# Gate_Drive.net
KiCad netlist of a schematic drawn in Altium Designer
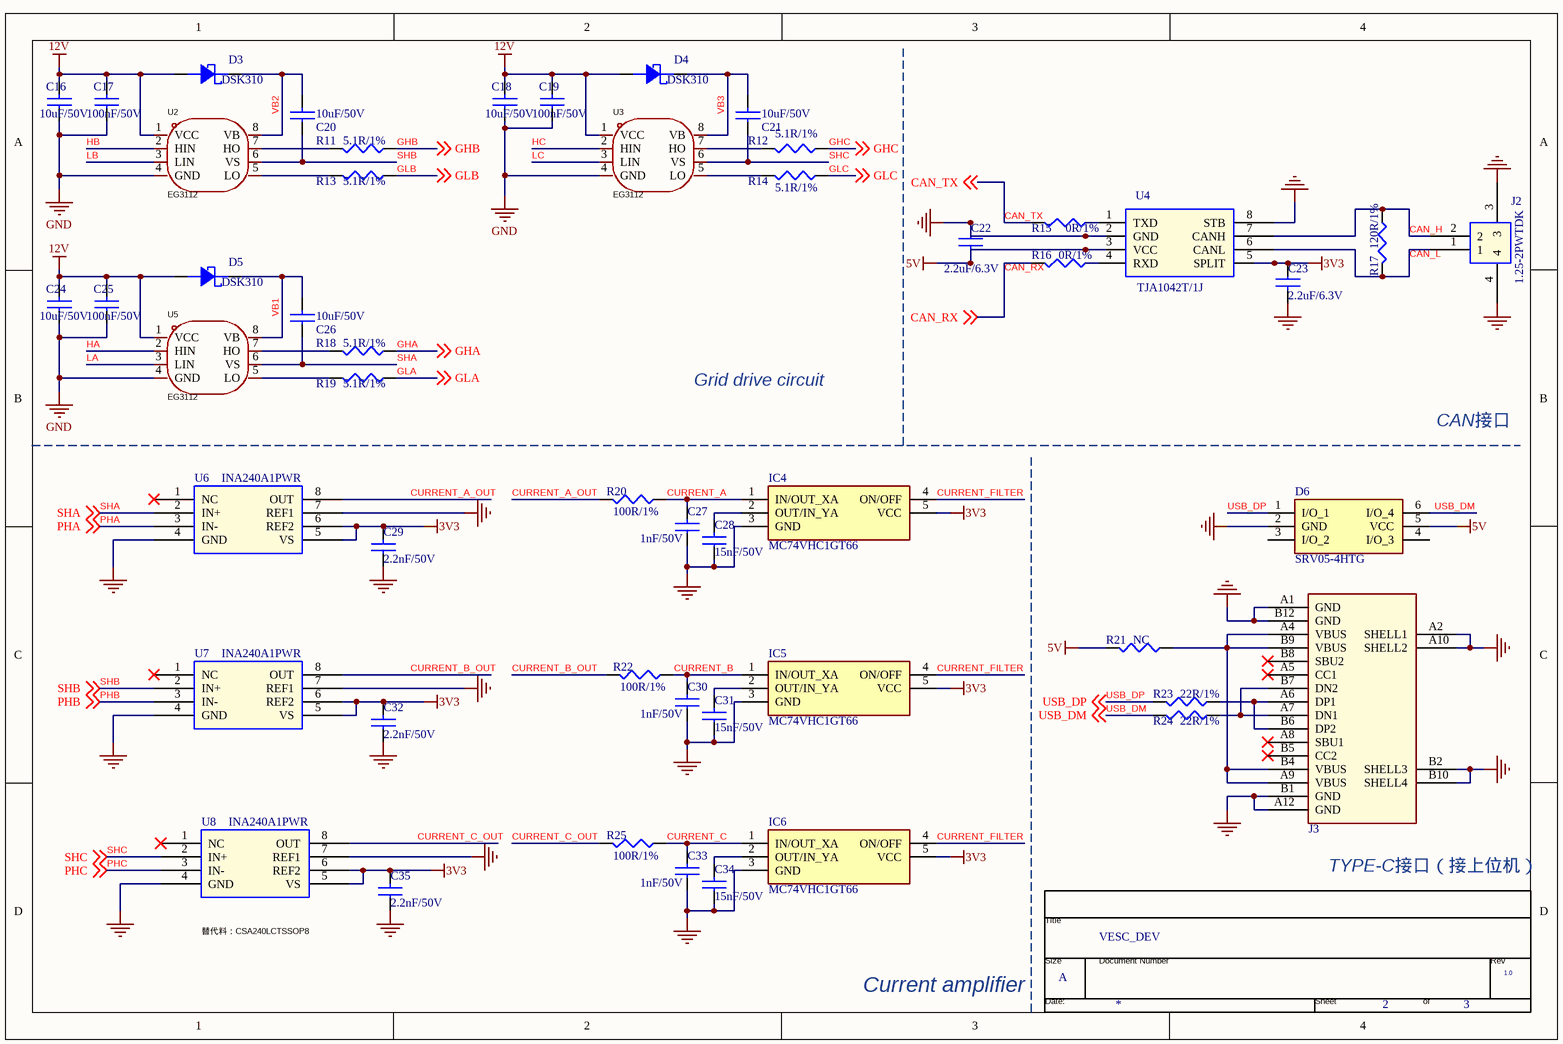
[diagram p0: Gate_Drive.SchDoc]

(export (version "E")
  (design (tool "Eeschema 10.0.6"))
  (components
    (comp (ref "C16") (value "10uF/50V") (footprint "C0603") (libsource (lib "*") (part "CAP NP")))
    (comp (ref "C17") (value "100nF/50V") (footprint "C0603") (libsource (lib "*") (part "CAP NP")))
    (comp (ref "C18") (value "10uF/50V") (footprint "C0603") (libsource (lib "*") (part "CAP NP")))
    (comp (ref "C19") (value "100nF/50V") (footprint "C0603") (libsource (lib "*") (part "CAP NP")))
    (comp (ref "C20") (value "10uF/50V") (footprint "C0603") (libsource (lib "*") (part "CAP NP")))
    (comp (ref "C21") (value "10uF/50V") (footprint "C0603") (libsource (lib "*") (part "CAP NP")))
    (comp (ref "C22") (value "2.2uF/6.3V") (footprint "C0402") (libsource (lib "*") (part "CAP NP")))
    (comp (ref "C23") (value "2.2uF/6.3V") (footprint "C0402") (libsource (lib "*") (part "CAP NP")))
    (comp (ref "C24") (value "10uF/50V") (footprint "C0603") (libsource (lib "*") (part "CAP NP")))
    (comp (ref "C25") (value "100nF/50V") (footprint "C0603") (libsource (lib "*") (part "CAP NP")))
    (comp (ref "C26") (value "10uF/50V") (footprint "C0603") (libsource (lib "*") (part "CAP NP")))
    (comp (ref "C27") (value "1nF/50V") (footprint "C0402") (libsource (lib "*") (part "CAP NP")))
    (comp (ref "C28") (value "15nF/50V") (footprint "C0402") (libsource (lib "*") (part "CAP NP")))
    (comp (ref "C29") (value "2.2nF/50V") (footprint "C0402") (libsource (lib "*") (part "CAP NP")))
    (comp (ref "C30") (value "1nF/50V") (footprint "C0402") (libsource (lib "*") (part "CAP NP")))
    (comp (ref "C31") (value "15nF/50V") (footprint "C0402") (libsource (lib "*") (part "CAP NP")))
    (comp (ref "C32") (value "2.2nF/50V") (footprint "C0402") (libsource (lib "*") (part "CAP NP")))
    (comp (ref "C33") (value "1nF/50V") (footprint "C0402") (libsource (lib "*") (part "CAP NP")))
    (comp (ref "C34") (value "15nF/50V") (footprint "C0402") (libsource (lib "*") (part "CAP NP")))
    (comp (ref "C35") (value "2.2nF/50V") (footprint "C0402") (libsource (lib "*") (part "CAP NP")))
    (comp (ref "D3") (value "DSK310") (footprint "SOD-123F") (libsource (lib "*") (part "DIODE SCHOTTKY21")))
    (comp (ref "D4") (value "DSK310") (footprint "SOD-123F") (libsource (lib "*") (part "DIODE SCHOTTKY21")))
    (comp (ref "D5") (value "DSK310") (footprint "SOD-123F") (libsource (lib "*") (part "DIODE SCHOTTKY21")))
    (comp (ref "D6")
      (value "SRV05-4HTG")
      (footprint "SamacSys:SOT95P280X145-6N")
      (description "TVS Diode (Uni-directional)")
      (fields (field (name "MOUSER PART NUMBER") "576-SRV05-4HTG"))
      (libsource (lib "VESC_DEVICE_Library") (part "SRV05-4HTG"))
    )
    (comp (ref "IC4")
      (value "MC74VHC1GT66")
      (footprint "SamacSys:SOT95P275X110-5N")
      (description "Integrated Circuit")
      (libsource (lib "VESC_DEVICE_Library") (part "MC74VHC1GT66"))
    )
    (comp (ref "IC5")
      (value "MC74VHC1GT66")
      (footprint "SamacSys:SOT95P275X110-5N")
      (description "Integrated Circuit")
      (libsource (lib "VESC_DEVICE_Library") (part "MC74VHC1GT66"))
    )
    (comp (ref "IC6")
      (value "MC74VHC1GT66")
      (footprint "SamacSys:SOT95P275X110-5N")
      (description "Integrated Circuit")
      (libsource (lib "VESC_DEVICE_Library") (part "MC74VHC1GT66"))
    )
    (comp (ref "J2")
      (value "1.25-2PWTDK")
      (footprint "SMD-2P-1_25")
      (libsource (lib "*") (part "1.25-2PWTDK"))
    )
    (comp (ref "J3")
      (value "TYPE-C 16PLC-H10.0")
      (footprint "TYPE-C-TH_16PLC-H10.0")
      (description "连接器类型:Type-C;标准:USB 3.1;公母:母;安装方式:直插;触点数量:16P;端口数量:1;额定电流 - 电源:5A;触头材质:-;触头镀层:-;工作温度范围:-40℃~+85℃;")
      (fields (field (name "MANUFACTURER") "SHOU HAN(首韩)"))
      (libsource (lib "VESC_DEVICE_Library") (part "TYPE-C 16PLC-H10.0"))
    )
    (comp (ref "R11") (value "5.1R/1%") (footprint "R0603") (libsource (lib "*") (part "RESISTOR")))
    (comp (ref "R12") (value "5.1R/1%") (footprint "R0603") (libsource (lib "*") (part "RESISTOR")))
    (comp (ref "R13") (value "5.1R/1%") (footprint "R0603") (libsource (lib "*") (part "RESISTOR")))
    (comp (ref "R14") (value "5.1R/1%") (footprint "R0603") (libsource (lib "*") (part "RESISTOR")))
    (comp (ref "R15") (value "0R/1%") (footprint "R0402") (libsource (lib "*") (part "RESISTOR")))
    (comp (ref "R16") (value "0R/1%") (footprint "R0402") (libsource (lib "*") (part "RESISTOR")))
    (comp (ref "R17") (value "120R/1%") (footprint "R0402") (libsource (lib "*") (part "RESISTOR")))
    (comp (ref "R18") (value "5.1R/1%") (footprint "R0603") (libsource (lib "*") (part "RESISTOR")))
    (comp (ref "R19") (value "5.1R/1%") (footprint "R0603") (libsource (lib "*") (part "RESISTOR")))
    (comp (ref "R20") (value "100R/1%") (footprint "R0402") (libsource (lib "*") (part "RESISTOR")))
    (comp (ref "R21") (value "NC") (footprint "R0603") (libsource (lib "*") (part "RESISTOR")))
    (comp (ref "R22") (value "100R/1%") (footprint "R0402") (libsource (lib "*") (part "RESISTOR")))
    (comp (ref "R23") (value "22R/1%") (footprint "R0402") (libsource (lib "*") (part "RESISTOR")))
    (comp (ref "R24") (value "22R/1%") (footprint "R0402") (libsource (lib "*") (part "RESISTOR")))
    (comp (ref "R25") (value "100R/1%") (footprint "R0402") (libsource (lib "*") (part "RESISTOR")))
    (comp (ref "U2")
      (value "EG3112")
      (footprint "SOIC-8_L4.9-W3.9-P1.27-LS6.0-BL")
      (fields (field (name "MANUFACTURER") "EG(屹晶微)"))
      (libsource (lib "VESC_DEVICE_Library") (part "EG3112"))
    )
    (comp (ref "U3")
      (value "EG3112")
      (footprint "SOIC-8_L4.9-W3.9-P1.27-LS6.0-BL")
      (fields (field (name "MANUFACTURER") "EG(屹晶微)"))
      (libsource (lib "VESC_DEVICE_Library") (part "EG3112"))
    )
    (comp (ref "U4") (value "TJA1042T/1J") (footprint "SOP-8") (libsource (lib "*") (part "TJA1042T/1J")))
    (comp (ref "U5")
      (value "EG3112")
      (footprint "SOIC-8_L4.9-W3.9-P1.27-LS6.0-BL")
      (fields (field (name "MANUFACTURER") "EG(屹晶微)"))
      (libsource (lib "VESC_DEVICE_Library") (part "EG3112"))
    )
    (comp (ref "U6") (value "INA240A1PWR") (footprint "TSSOP-8") (libsource (lib "*") (part "INA240A1PWR")))
    (comp (ref "U7") (value "INA240A1PWR") (footprint "TSSOP-8") (libsource (lib "*") (part "INA240A1PWR")))
    (comp (ref "U8") (value "INA240A1PWR") (footprint "TSSOP-8") (libsource (lib "*") (part "INA240A1PWR")))
  )
  (nets
    (net (code "1") (name "/CAN_H") (class "Default")
      (node (ref "J2") (pin "2") (pinfunction "2_2") (pintype "passive"))
      (node (ref "R17") (pin "1") (pinfunction "1_1") (pintype "passive"))
      (node (ref "U4") (pin "7") (pinfunction "CANH_7") (pintype "passive"))
    )
    (net (code "2") (name "/CAN_L") (class "Default")
      (node (ref "J2") (pin "1") (pinfunction "1_1") (pintype "passive"))
      (node (ref "R17") (pin "2") (pinfunction "2_2") (pintype "passive"))
      (node (ref "U4") (pin "6") (pinfunction "CANL_6") (pintype "passive"))
    )
    (net (code "3") (name "/CURRENT_A") (class "Default")
      (node (ref "C27") (pin "2") (pinfunction "2_2") (pintype "passive"))
      (node (ref "IC4") (pin "1") (pinfunction "IN/OUT_XA_1") (pintype "passive"))
      (node (ref "R20") (pin "1") (pinfunction "1_1") (pintype "passive"))
    )
    (net (code "4") (name "/CURRENT_A_OUT") (class "Default")
      (node (ref "R20") (pin "2") (pinfunction "2_2") (pintype "passive"))
      (node (ref "U6") (pin "8") (pinfunction "OUT_8") (pintype "passive"))
    )
    (net (code "5") (name "/CURRENT_B") (class "Default")
      (node (ref "C30") (pin "2") (pinfunction "2_2") (pintype "passive"))
      (node (ref "IC5") (pin "1") (pinfunction "IN/OUT_XA_1") (pintype "passive"))
      (node (ref "R22") (pin "1") (pinfunction "1_1") (pintype "passive"))
    )
    (net (code "6") (name "/CURRENT_B_OUT") (class "Default")
      (node (ref "R22") (pin "2") (pinfunction "2_2") (pintype "passive"))
      (node (ref "U7") (pin "8") (pinfunction "OUT_8") (pintype "passive"))
    )
    (net (code "7") (name "/CURRENT_C") (class "Default")
      (node (ref "C33") (pin "2") (pinfunction "2_2") (pintype "passive"))
      (node (ref "IC6") (pin "1") (pinfunction "IN/OUT_XA_1") (pintype "passive"))
      (node (ref "R25") (pin "1") (pinfunction "1_1") (pintype "passive"))
    )
    (net (code "8") (name "/CURRENT_C_OUT") (class "Default")
      (node (ref "R25") (pin "2") (pinfunction "2_2") (pintype "passive"))
      (node (ref "U8") (pin "8") (pinfunction "OUT_8") (pintype "passive"))
    )
    (net (code "9") (name "/CURRENT_FILTER") (class "Default")
      (node (ref "IC4") (pin "4") (pinfunction "ON/OFF_4") (pintype "passive"))
      (node (ref "IC5") (pin "4") (pinfunction "ON/OFF_4") (pintype "passive"))
      (node (ref "IC6") (pin "4") (pinfunction "ON/OFF_4") (pintype "passive"))
    )
    (net (code "10") (name "/HA") (class "Default")
      (node (ref "U5") (pin "2") (pinfunction "HIN_2") (pintype "passive"))
    )
    (net (code "11") (name "/HB") (class "Default")
      (node (ref "U2") (pin "2") (pinfunction "HIN_2") (pintype "passive"))
    )
    (net (code "12") (name "/HC") (class "Default")
      (node (ref "U3") (pin "2") (pinfunction "HIN_2") (pintype "passive"))
    )
    (net (code "13") (name "/LA") (class "Default")
      (node (ref "U5") (pin "3") (pinfunction "LIN_3") (pintype "passive"))
    )
    (net (code "14") (name "/LB") (class "Default")
      (node (ref "U2") (pin "3") (pinfunction "LIN_3") (pintype "passive"))
    )
    (net (code "15") (name "/LC") (class "Default")
      (node (ref "U3") (pin "3") (pinfunction "LIN_3") (pintype "passive"))
    )
    (net (code "16") (name "/VB1") (class "Default")
      (node (ref "C26") (pin "2") (pinfunction "2_2") (pintype "passive"))
      (node (ref "D5") (pin "1") (pinfunction "K_1") (pintype "passive"))
      (node (ref "U5") (pin "8") (pinfunction "VB_8") (pintype "passive"))
    )
    (net (code "17") (name "/VB2") (class "Default")
      (node (ref "C20") (pin "2") (pinfunction "2_2") (pintype "passive"))
      (node (ref "D3") (pin "1") (pinfunction "K_1") (pintype "passive"))
      (node (ref "U2") (pin "8") (pinfunction "VB_8") (pintype "passive"))
    )
    (net (code "18") (name "/VB3") (class "Default")
      (node (ref "C21") (pin "2") (pinfunction "2_2") (pintype "passive"))
      (node (ref "D4") (pin "1") (pinfunction "K_1") (pintype "passive"))
      (node (ref "U3") (pin "8") (pinfunction "VB_8") (pintype "passive"))
    )
    (net (code "19") (name "3V3") (class "Default")
      (node (ref "C23") (pin "1") (pinfunction "1_1") (pintype "passive"))
      (node (ref "C29") (pin "2") (pinfunction "2_2") (pintype "passive"))
      (node (ref "C32") (pin "2") (pinfunction "2_2") (pintype "passive"))
      (node (ref "C35") (pin "2") (pinfunction "2_2") (pintype "passive"))
      (node (ref "IC4") (pin "5") (pinfunction "VCC_5") (pintype "passive"))
      (node (ref "IC5") (pin "5") (pinfunction "VCC_5") (pintype "passive"))
      (node (ref "IC6") (pin "5") (pinfunction "VCC_5") (pintype "passive"))
      (node (ref "U4") (pin "5") (pinfunction "SPLIT_5") (pintype "passive"))
      (node (ref "U6") (pin "5") (pinfunction "VS_5") (pintype "passive"))
      (node (ref "U6") (pin "6") (pinfunction "REF2_6") (pintype "passive"))
      (node (ref "U7") (pin "5") (pinfunction "VS_5") (pintype "passive"))
      (node (ref "U7") (pin "6") (pinfunction "REF2_6") (pintype "passive"))
      (node (ref "U8") (pin "5") (pinfunction "VS_5") (pintype "passive"))
      (node (ref "U8") (pin "6") (pinfunction "REF2_6") (pintype "passive"))
    )
    (net (code "20") (name "5V") (class "Default")
      (node (ref "C22") (pin "2") (pinfunction "2_2") (pintype "passive"))
      (node (ref "D6") (pin "5") (pinfunction "VCC_5") (pintype "passive"))
      (node (ref "R21") (pin "2") (pinfunction "2_2") (pintype "passive"))
      (node (ref "U4") (pin "3") (pinfunction "VCC_3") (pintype "passive"))
    )
    (net (code "21") (name "12V") (class "Default")
      (node (ref "C16") (pin "2") (pinfunction "2_2") (pintype "passive"))
      (node (ref "C17") (pin "2") (pinfunction "2_2") (pintype "passive"))
      (node (ref "C18") (pin "2") (pinfunction "2_2") (pintype "passive"))
      (node (ref "C19") (pin "2") (pinfunction "2_2") (pintype "passive"))
      (node (ref "C24") (pin "2") (pinfunction "2_2") (pintype "passive"))
      (node (ref "C25") (pin "2") (pinfunction "2_2") (pintype "passive"))
      (node (ref "D3") (pin "2") (pinfunction "A_2") (pintype "passive"))
      (node (ref "D4") (pin "2") (pinfunction "A_2") (pintype "passive"))
      (node (ref "D5") (pin "2") (pinfunction "A_2") (pintype "passive"))
      (node (ref "U2") (pin "1") (pinfunction "VCC_1") (pintype "passive"))
      (node (ref "U3") (pin "1") (pinfunction "VCC_1") (pintype "passive"))
      (node (ref "U5") (pin "1") (pinfunction "VCC_1") (pintype "passive"))
    )
    (net (code "22") (name "CAN_RX") (class "Default")
      (node (ref "R16") (pin "2") (pinfunction "2_2") (pintype "passive"))
    )
    (net (code "23") (name "CAN_TX") (class "Default")
      (node (ref "R15") (pin "2") (pinfunction "2_2") (pintype "passive"))
    )
    (net (code "24") (name "GHA") (class "Default")
      (node (ref "R18") (pin "1") (pinfunction "1_1") (pintype "passive"))
    )
    (net (code "25") (name "GHB") (class "Default")
      (node (ref "R11") (pin "1") (pinfunction "1_1") (pintype "passive"))
    )
    (net (code "26") (name "GHC") (class "Default")
      (node (ref "R12") (pin "1") (pinfunction "1_1") (pintype "passive"))
    )
    (net (code "27") (name "GLA") (class "Default")
      (node (ref "R19") (pin "1") (pinfunction "1_1") (pintype "passive"))
    )
    (net (code "28") (name "GLB") (class "Default")
      (node (ref "R13") (pin "1") (pinfunction "1_1") (pintype "passive"))
    )
    (net (code "29") (name "GLC") (class "Default")
      (node (ref "R14") (pin "1") (pinfunction "1_1") (pintype "passive"))
    )
    (net (code "30") (name "GND") (class "Default")
      (node (ref "C16") (pin "1") (pinfunction "1_1") (pintype "passive"))
      (node (ref "C17") (pin "1") (pinfunction "1_1") (pintype "passive"))
      (node (ref "C18") (pin "1") (pinfunction "1_1") (pintype "passive"))
      (node (ref "C19") (pin "1") (pinfunction "1_1") (pintype "passive"))
      (node (ref "C22") (pin "1") (pinfunction "1_1") (pintype "passive"))
      (node (ref "C23") (pin "2") (pinfunction "2_2") (pintype "passive"))
      (node (ref "C24") (pin "1") (pinfunction "1_1") (pintype "passive"))
      (node (ref "C25") (pin "1") (pinfunction "1_1") (pintype "passive"))
      (node (ref "C27") (pin "1") (pinfunction "1_1") (pintype "passive"))
      (node (ref "C28") (pin "1") (pinfunction "1_1") (pintype "passive"))
      (node (ref "C29") (pin "1") (pinfunction "1_1") (pintype "passive"))
      (node (ref "C30") (pin "1") (pinfunction "1_1") (pintype "passive"))
      (node (ref "C31") (pin "1") (pinfunction "1_1") (pintype "passive"))
      (node (ref "C32") (pin "1") (pinfunction "1_1") (pintype "passive"))
      (node (ref "C33") (pin "1") (pinfunction "1_1") (pintype "passive"))
      (node (ref "C34") (pin "1") (pinfunction "1_1") (pintype "passive"))
      (node (ref "C35") (pin "1") (pinfunction "1_1") (pintype "passive"))
      (node (ref "D6") (pin "2") (pinfunction "GND_2") (pintype "passive"))
      (node (ref "IC4") (pin "3") (pinfunction "GND_3") (pintype "passive"))
      (node (ref "IC5") (pin "3") (pinfunction "GND_3") (pintype "passive"))
      (node (ref "IC6") (pin "3") (pinfunction "GND_3") (pintype "passive"))
      (node (ref "J2") (pin "3") (pinfunction "3_3") (pintype "passive"))
      (node (ref "J2") (pin "4") (pinfunction "4_4") (pintype "passive"))
      (node (ref "J3") (pin "A1") (pinfunction "GND_A1") (pintype "power_in"))
      (node (ref "J3") (pin "A10") (pinfunction "SHELL2_A10") (pintype "power_in"))
      (node (ref "J3") (pin "A12") (pinfunction "GND_A12") (pintype "power_in"))
      (node (ref "J3") (pin "A2") (pinfunction "SHELL1_A2") (pintype "power_in"))
      (node (ref "J3") (pin "B1") (pinfunction "GND_B1") (pintype "power_in"))
      (node (ref "J3") (pin "B10") (pinfunction "SHELL4_B10") (pintype "power_in"))
      (node (ref "J3") (pin "B12") (pinfunction "GND_B12") (pintype "power_in"))
      (node (ref "J3") (pin "B2") (pinfunction "SHELL3_B2") (pintype "power_in"))
      (node (ref "U2") (pin "4") (pinfunction "GND_4") (pintype "passive"))
      (node (ref "U3") (pin "4") (pinfunction "GND_4") (pintype "passive"))
      (node (ref "U4") (pin "2") (pinfunction "GND_2") (pintype "passive"))
      (node (ref "U4") (pin "8") (pinfunction "STB_8") (pintype "passive"))
      (node (ref "U5") (pin "4") (pinfunction "GND_4") (pintype "passive"))
      (node (ref "U6") (pin "4") (pinfunction "GND_4") (pintype "passive"))
      (node (ref "U6") (pin "7") (pinfunction "REF1_7") (pintype "passive"))
      (node (ref "U7") (pin "4") (pinfunction "GND_4") (pintype "passive"))
      (node (ref "U7") (pin "7") (pinfunction "REF1_7") (pintype "passive"))
      (node (ref "U8") (pin "4") (pinfunction "GND_4") (pintype "passive"))
      (node (ref "U8") (pin "7") (pinfunction "REF1_7") (pintype "passive"))
    )
    (net (code "31") (name "Net-(IC4-OUT{slash}IN_YA)") (class "Default")
      (node (ref "C28") (pin "2") (pinfunction "2_2") (pintype "passive"))
      (node (ref "IC4") (pin "2") (pinfunction "OUT/IN_YA_2") (pintype "passive"))
    )
    (net (code "32") (name "Net-(IC5-OUT{slash}IN_YA)") (class "Default")
      (node (ref "C31") (pin "2") (pinfunction "2_2") (pintype "passive"))
      (node (ref "IC5") (pin "2") (pinfunction "OUT/IN_YA_2") (pintype "passive"))
    )
    (net (code "33") (name "Net-(IC6-OUT{slash}IN_YA)") (class "Default")
      (node (ref "C34") (pin "2") (pinfunction "2_2") (pintype "passive"))
      (node (ref "IC6") (pin "2") (pinfunction "OUT/IN_YA_2") (pintype "passive"))
    )
    (net (code "34") (name "Net-(J3-DN1)") (class "Default")
      (node (ref "J3") (pin "A7") (pinfunction "DN1_A7") (pintype "passive"))
      (node (ref "J3") (pin "B7") (pinfunction "DN2_B7") (pintype "passive"))
      (node (ref "R24") (pin "1") (pinfunction "1_1") (pintype "passive"))
    )
    (net (code "35") (name "Net-(J3-DP1)") (class "Default")
      (node (ref "J3") (pin "A6") (pinfunction "DP1_A6") (pintype "passive"))
      (node (ref "J3") (pin "B6") (pinfunction "DP2_B6") (pintype "passive"))
      (node (ref "R23") (pin "1") (pinfunction "1_1") (pintype "passive"))
    )
    (net (code "36") (name "Net-(J3-VBUS-PadA4)") (class "Default")
      (node (ref "J3") (pin "A4") (pinfunction "VBUS_A4") (pintype "power_in"))
      (node (ref "J3") (pin "A9") (pinfunction "VBUS_A9") (pintype "power_in"))
      (node (ref "J3") (pin "B4") (pinfunction "VBUS_B4") (pintype "power_in"))
      (node (ref "J3") (pin "B9") (pinfunction "VBUS_B9") (pintype "power_in"))
      (node (ref "R21") (pin "1") (pinfunction "1_1") (pintype "passive"))
    )
    (net (code "37") (name "Net-(U2-HO)") (class "Default")
      (node (ref "R11") (pin "2") (pinfunction "2_2") (pintype "passive"))
      (node (ref "U2") (pin "7") (pinfunction "HO_7") (pintype "passive"))
    )
    (net (code "38") (name "Net-(U2-LO)") (class "Default")
      (node (ref "R13") (pin "2") (pinfunction "2_2") (pintype "passive"))
      (node (ref "U2") (pin "5") (pinfunction "LO_5") (pintype "passive"))
    )
    (net (code "39") (name "Net-(U3-HO)") (class "Default")
      (node (ref "R12") (pin "2") (pinfunction "2_2") (pintype "passive"))
      (node (ref "U3") (pin "7") (pinfunction "HO_7") (pintype "passive"))
    )
    (net (code "40") (name "Net-(U3-LO)") (class "Default")
      (node (ref "R14") (pin "2") (pinfunction "2_2") (pintype "passive"))
      (node (ref "U3") (pin "5") (pinfunction "LO_5") (pintype "passive"))
    )
    (net (code "41") (name "Net-(U4-RXD)") (class "Default")
      (node (ref "R16") (pin "1") (pinfunction "1_1") (pintype "passive"))
      (node (ref "U4") (pin "4") (pinfunction "RXD_4") (pintype "passive"))
    )
    (net (code "42") (name "Net-(U4-TXD)") (class "Default")
      (node (ref "R15") (pin "1") (pinfunction "1_1") (pintype "passive"))
      (node (ref "U4") (pin "1") (pinfunction "TXD_1") (pintype "passive"))
    )
    (net (code "43") (name "Net-(U5-HO)") (class "Default")
      (node (ref "R18") (pin "2") (pinfunction "2_2") (pintype "passive"))
      (node (ref "U5") (pin "7") (pinfunction "HO_7") (pintype "passive"))
    )
    (net (code "44") (name "Net-(U5-LO)") (class "Default")
      (node (ref "R19") (pin "2") (pinfunction "2_2") (pintype "passive"))
      (node (ref "U5") (pin "5") (pinfunction "LO_5") (pintype "passive"))
    )
    (net (code "45") (name "PHA") (class "Default")
      (node (ref "U6") (pin "3") (pinfunction "IN-_3") (pintype "passive"))
    )
    (net (code "46") (name "PHB") (class "Default")
      (node (ref "U7") (pin "3") (pinfunction "IN-_3") (pintype "passive"))
    )
    (net (code "47") (name "PHC") (class "Default")
      (node (ref "U8") (pin "3") (pinfunction "IN-_3") (pintype "passive"))
    )
    (net (code "48") (name "SHA") (class "Default")
      (node (ref "C26") (pin "1") (pinfunction "1_1") (pintype "passive"))
      (node (ref "U5") (pin "6") (pinfunction "VS_6") (pintype "passive"))
      (node (ref "U6") (pin "2") (pinfunction "IN+_2") (pintype "passive"))
    )
    (net (code "49") (name "SHB") (class "Default")
      (node (ref "C20") (pin "1") (pinfunction "1_1") (pintype "passive"))
      (node (ref "U2") (pin "6") (pinfunction "VS_6") (pintype "passive"))
      (node (ref "U7") (pin "2") (pinfunction "IN+_2") (pintype "passive"))
    )
    (net (code "50") (name "SHC") (class "Default")
      (node (ref "C21") (pin "1") (pinfunction "1_1") (pintype "passive"))
      (node (ref "U3") (pin "6") (pinfunction "VS_6") (pintype "passive"))
      (node (ref "U8") (pin "2") (pinfunction "IN+_2") (pintype "passive"))
    )
    (net (code "51") (name "USB_DM") (class "Default")
      (node (ref "D6") (pin "6") (pinfunction "I/O_4_6") (pintype "passive"))
      (node (ref "R24") (pin "2") (pinfunction "2_2") (pintype "passive"))
    )
    (net (code "52") (name "USB_DP") (class "Default")
      (node (ref "D6") (pin "1") (pinfunction "I/O_1_1") (pintype "passive"))
      (node (ref "R23") (pin "2") (pinfunction "2_2") (pintype "passive"))
    )
    (net (code "53") (name "unconnected-(D6-I{slash}O_2-Pad3)") (class "Default")
      (node (ref "D6") (pin "3") (pinfunction "I/O_2_3") (pintype "passive"))
    )
    (net (code "54") (name "unconnected-(D6-I{slash}O_3-Pad4)") (class "Default")
      (node (ref "D6") (pin "4") (pinfunction "I/O_3_4") (pintype "passive"))
    )
    (net (code "55") (name "unconnected-(J3-CC1-PadA5)") (class "Default")
      (node (ref "J3") (pin "A5") (pinfunction "CC1_A5") (pintype "passive+no_connect"))
    )
    (net (code "56") (name "unconnected-(J3-CC2-PadB5)") (class "Default")
      (node (ref "J3") (pin "B5") (pinfunction "CC2_B5") (pintype "passive+no_connect"))
    )
    (net (code "57") (name "unconnected-(J3-SBU1-PadA8)") (class "Default")
      (node (ref "J3") (pin "A8") (pinfunction "SBU1_A8") (pintype "passive+no_connect"))
    )
    (net (code "58") (name "unconnected-(J3-SBU2-PadB8)") (class "Default")
      (node (ref "J3") (pin "B8") (pinfunction "SBU2_B8") (pintype "passive+no_connect"))
    )
    (net (code "59") (name "unconnected-(U6-NC-Pad1)") (class "Default")
      (node (ref "U6") (pin "1") (pinfunction "NC_1") (pintype "passive+no_connect"))
    )
    (net (code "60") (name "unconnected-(U7-NC-Pad1)") (class "Default")
      (node (ref "U7") (pin "1") (pinfunction "NC_1") (pintype "passive+no_connect"))
    )
    (net (code "61") (name "unconnected-(U8-NC-Pad1)") (class "Default")
      (node (ref "U8") (pin "1") (pinfunction "NC_1") (pintype "passive+no_connect"))
    )
  )
)
